# RFM12DipAdapter.net
KiCad netlist of a schematic drawn in EAGLE
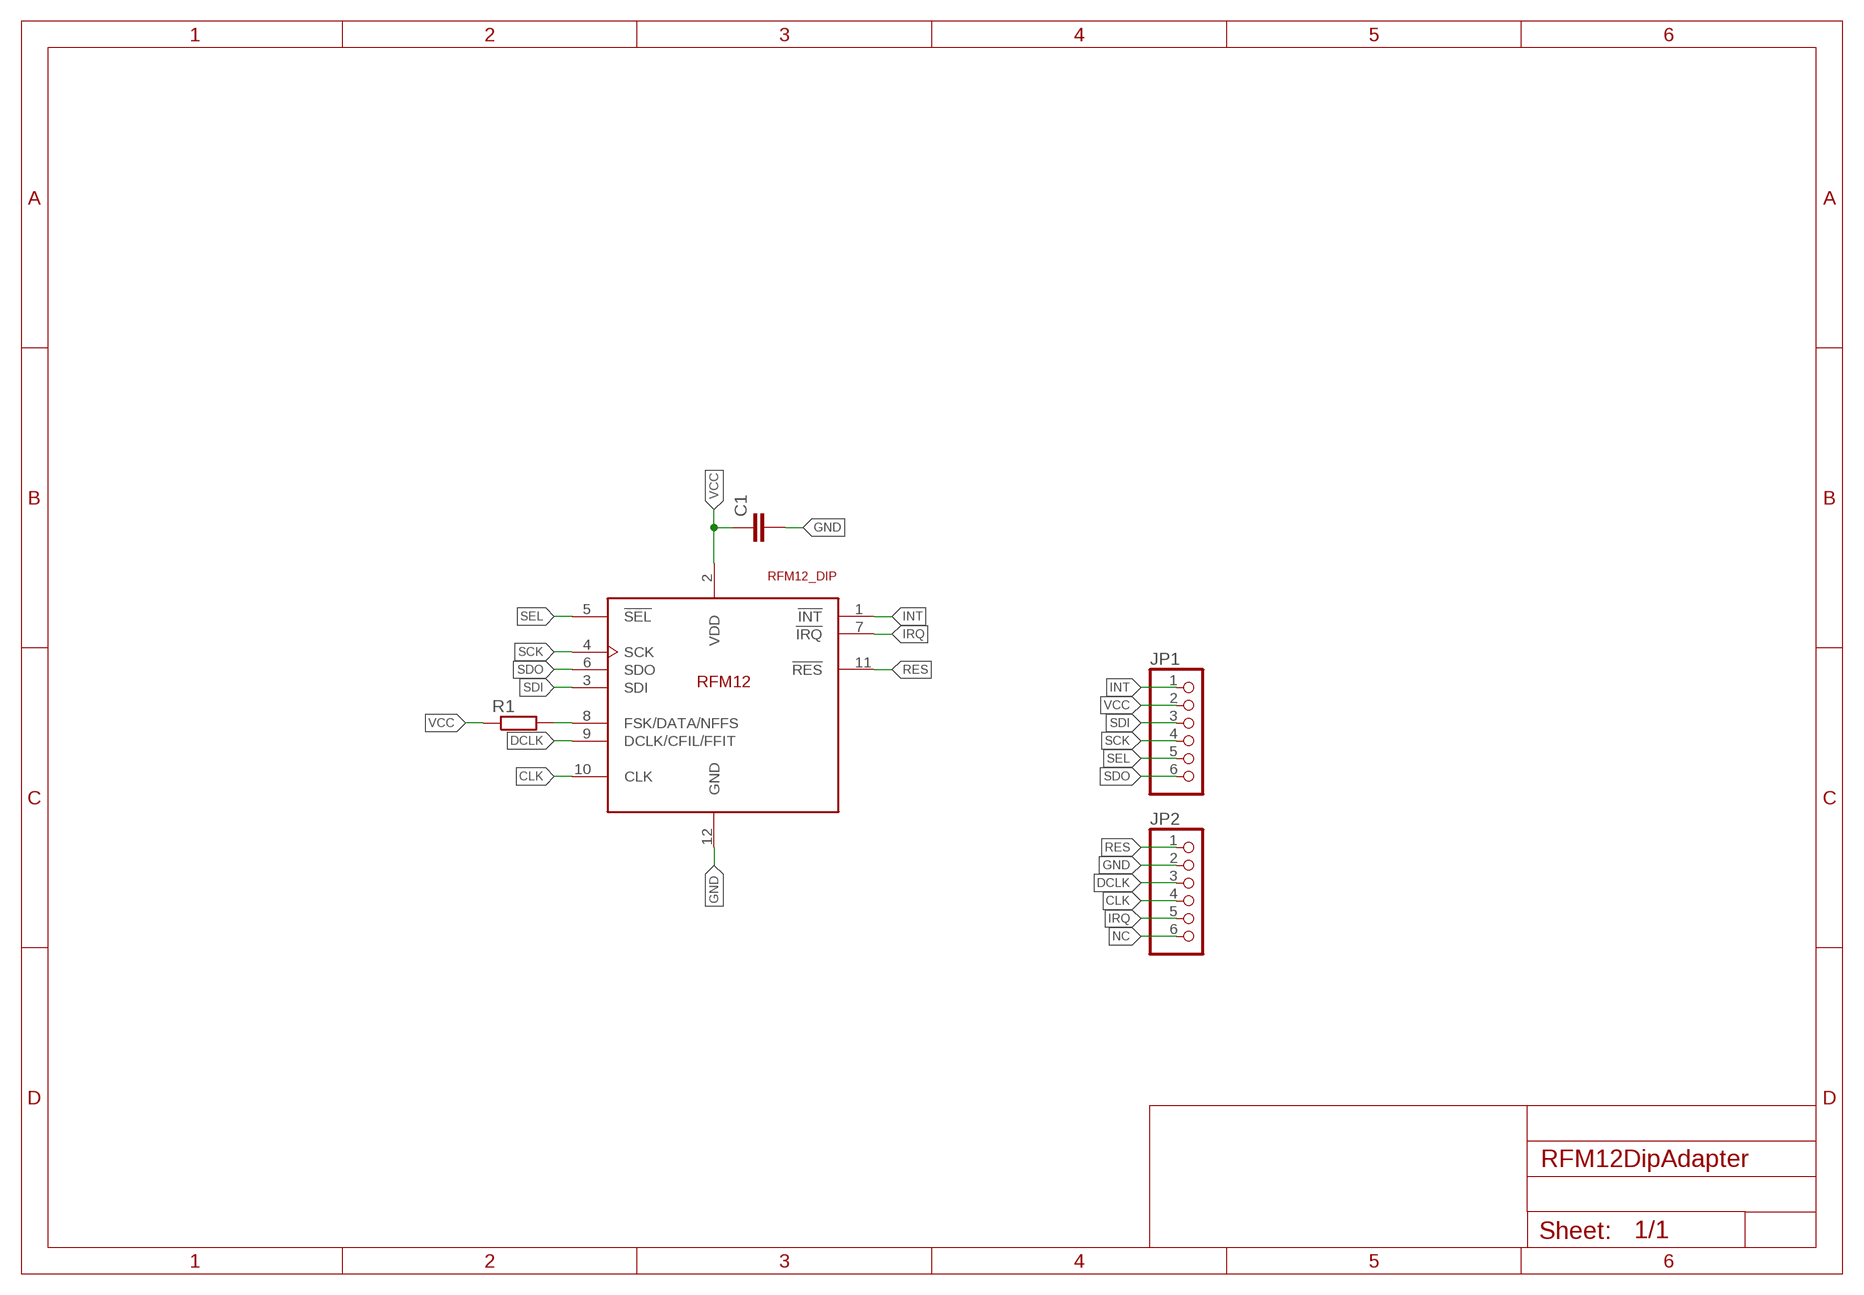
[diagram p0: schematic, sheet 1]

(export (version "E")
  (design (tool "Eeschema 10.0.6"))
  (components
    (comp (ref "C1")
      (value "C-EUC0805")
      (footprint "eagle-import:C0805")
      (libsource (lib "eagle-import") (part "C-EUC0805"))
    )
    (comp (ref "JP1")
      (value "PINHD-1X6")
      (footprint "eagle-import:1X06")
      (libsource (lib "eagle-import") (part "PINHD-1X6"))
    )
    (comp (ref "JP2")
      (value "PINHD-1X6")
      (footprint "eagle-import:1X06")
      (libsource (lib "eagle-import") (part "PINHD-1X6"))
    )
    (comp (ref "R1")
      (value "R-EU_R1206")
      (footprint "eagle-import:R1206")
      (libsource (lib "eagle-import") (part "R-EU_R1206"))
    )
    (comp (ref "U$1")
      (value "RFM12_DIP")
      (footprint "eagle-import:DIL-2MM-2X06")
      (libsource (lib "eagle-import") (part "RFM12_DIP"))
    )
  )
  (nets
    (net (code "1") (name "CLK") (class "Default")
      (node (ref "JP2") (pin "4") (pinfunction "4_4") (pintype "passive"))
      (node (ref "U$1") (pin "10") (pinfunction "CLK_10") (pintype "output"))
    )
    (net (code "2") (name "DCLK") (class "Default")
      (node (ref "JP2") (pin "3") (pinfunction "3_3") (pintype "passive"))
      (node (ref "U$1") (pin "9") (pinfunction "DCLK/CFIL/FFIT_9") (pintype "bidirectional"))
    )
    (net (code "3") (name "GND") (class "Default")
      (node (ref "C1") (pin "2") (pinfunction "2_2") (pintype "passive"))
      (node (ref "JP2") (pin "2") (pinfunction "2_2") (pintype "passive"))
      (node (ref "U$1") (pin "12") (pinfunction "GND_12") (pintype "passive"))
    )
    (net (code "4") (name "INT") (class "Default")
      (node (ref "JP1") (pin "1") (pinfunction "1_1") (pintype "passive"))
      (node (ref "U$1") (pin "1") (pinfunction "~{INT}_1") (pintype "bidirectional"))
    )
    (net (code "5") (name "IRQ") (class "Default")
      (node (ref "JP2") (pin "5") (pinfunction "5_5") (pintype "passive"))
      (node (ref "U$1") (pin "7") (pinfunction "~{IRQ}_7") (pintype "output"))
    )
    (net (code "6") (name "NC") (class "Default")
      (node (ref "JP2") (pin "6") (pinfunction "6_6") (pintype "passive"))
    )
    (net (code "7") (name "Net-(U$1-FSK{slash}DATA{slash}NFFS)") (class "Default")
      (node (ref "R1") (pin "2") (pinfunction "2_2") (pintype "passive"))
      (node (ref "U$1") (pin "8") (pinfunction "FSK/DATA/NFFS_8") (pintype "bidirectional"))
    )
    (net (code "8") (name "RES") (class "Default")
      (node (ref "JP2") (pin "1") (pinfunction "1_1") (pintype "passive"))
      (node (ref "U$1") (pin "11") (pinfunction "~{RES}_11") (pintype "bidirectional"))
    )
    (net (code "9") (name "SCK") (class "Default")
      (node (ref "JP1") (pin "4") (pinfunction "4_4") (pintype "passive"))
      (node (ref "U$1") (pin "4") (pinfunction "SCK_4") (pintype "input"))
    )
    (net (code "10") (name "SDI") (class "Default")
      (node (ref "JP1") (pin "3") (pinfunction "3_3") (pintype "passive"))
      (node (ref "U$1") (pin "3") (pinfunction "SDI_3") (pintype "input"))
    )
    (net (code "11") (name "SDO") (class "Default")
      (node (ref "JP1") (pin "6") (pinfunction "6_6") (pintype "passive"))
      (node (ref "U$1") (pin "6") (pinfunction "SDO_6") (pintype "output"))
    )
    (net (code "12") (name "SEL") (class "Default")
      (node (ref "JP1") (pin "5") (pinfunction "5_5") (pintype "passive"))
      (node (ref "U$1") (pin "5") (pinfunction "~{SEL}_5") (pintype "input"))
    )
    (net (code "13") (name "VCC") (class "Default")
      (node (ref "C1") (pin "1") (pinfunction "1_1") (pintype "passive"))
      (node (ref "JP1") (pin "2") (pinfunction "2_2") (pintype "passive"))
      (node (ref "R1") (pin "1") (pinfunction "1_1") (pintype "passive"))
      (node (ref "U$1") (pin "2") (pinfunction "VDD_2") (pintype "power_in"))
    )
  )
)
